# STB_Spectrometer.net
KiCad netlist of a schematic drawn in Altium Designer
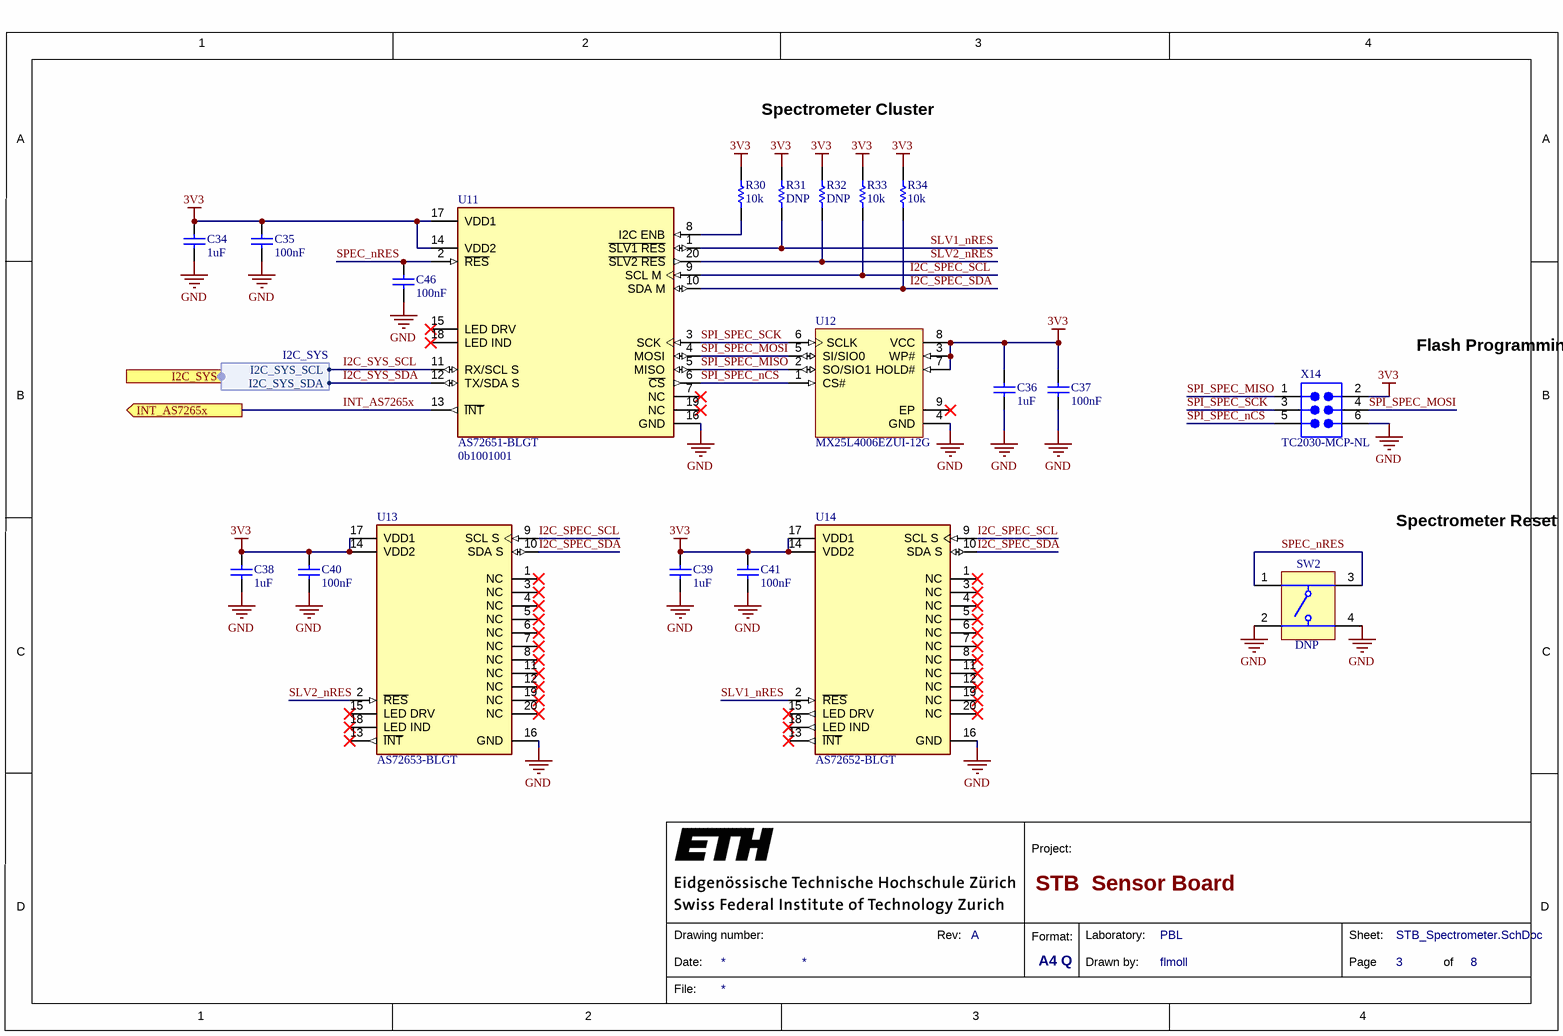
[diagram p0: STB_Spectrometer.SchDoc]

(export (version "E")
  (design (tool "Eeschema 10.0.6"))
  (components
    (comp (ref "C34")
      (value "1uF")
      (footprint "CAPC1608X90X35LL15T15")
      (fields (field (name "MANUFACTURER") "Kemet") (field (name "PART NUMBER") "C0603C105K4RACTU"))
      (libsource (lib "Altium Content Vault") (part "CAP"))
    )
    (comp (ref "C35")
      (value "100nF")
      (footprint "CAPC1050X55X23LL05T13")
      (description "Chip Capacitor, 100 nF, +/- 10%, 16 V, -55 to 125 degC, 0402 (1005 Metric), RoHS, Tape and Reel")
      (fields
        (field (name "MANUFACTURER") "Samsung Electro-Mechanics")
        (field (name "MANUFACTURER PART NUMBER") "CL05B104KO5NNNC")
      )
      (libsource (lib "Altium Content Vault") (part "CAP-NP-2"))
    )
    (comp (ref "C36")
      (value "1uF")
      (footprint "CAPC1608X90X35LL15T15")
      (fields (field (name "MANUFACTURER") "Kemet") (field (name "PART NUMBER") "C0603C105K4RACTU"))
      (libsource (lib "Altium Content Vault") (part "CAP"))
    )
    (comp (ref "C37")
      (value "100nF")
      (footprint "CAPC1050X55X23LL05T13")
      (description "Chip Capacitor, 100 nF, +/- 10%, 16 V, -55 to 125 degC, 0402 (1005 Metric), RoHS, Tape and Reel")
      (fields
        (field (name "MANUFACTURER") "Samsung Electro-Mechanics")
        (field (name "MANUFACTURER PART NUMBER") "CL05B104KO5NNNC")
      )
      (libsource (lib "Altium Content Vault") (part "CAP-NP-2"))
    )
    (comp (ref "C38")
      (value "1uF")
      (footprint "CAPC1608X90X35LL15T15")
      (fields (field (name "MANUFACTURER") "Kemet") (field (name "PART NUMBER") "C0603C105K4RACTU"))
      (libsource (lib "Altium Content Vault") (part "CAP"))
    )
    (comp (ref "C39")
      (value "1uF")
      (footprint "CAPC1608X90X35LL15T15")
      (fields (field (name "MANUFACTURER") "Kemet") (field (name "PART NUMBER") "C0603C105K4RACTU"))
      (libsource (lib "Altium Content Vault") (part "CAP"))
    )
    (comp (ref "C40")
      (value "100nF")
      (footprint "CAPC1050X55X23LL05T13")
      (description "Chip Capacitor, 100 nF, +/- 10%, 16 V, -55 to 125 degC, 0402 (1005 Metric), RoHS, Tape and Reel")
      (fields
        (field (name "MANUFACTURER") "Samsung Electro-Mechanics")
        (field (name "MANUFACTURER PART NUMBER") "CL05B104KO5NNNC")
      )
      (libsource (lib "Altium Content Vault") (part "CAP-NP-2"))
    )
    (comp (ref "C41")
      (value "100nF")
      (footprint "CAPC1050X55X23LL05T13")
      (description "Chip Capacitor, 100 nF, +/- 10%, 16 V, -55 to 125 degC, 0402 (1005 Metric), RoHS, Tape and Reel")
      (fields
        (field (name "MANUFACTURER") "Samsung Electro-Mechanics")
        (field (name "MANUFACTURER PART NUMBER") "CL05B104KO5NNNC")
      )
      (libsource (lib "Altium Content Vault") (part "CAP-NP-2"))
    )
    (comp (ref "C46")
      (value "100nF")
      (footprint "CAPC1050X55X23LL05T13")
      (description "Chip Capacitor, 100 nF, +/- 10%, 16 V, -55 to 125 degC, 0402 (1005 Metric), RoHS, Tape and Reel")
      (fields
        (field (name "MANUFACTURER") "Samsung Electro-Mechanics")
        (field (name "MANUFACTURER PART NUMBER") "CL05B104KO5NNNC")
      )
      (libsource (lib "Altium Content Vault") (part "CAP-NP-2"))
    )
    (comp (ref "R30")
      (value "10k")
      (footprint "RESC1005X40X25LL05T05")
      (description "Chip Resistor, 10 KOhm, +/- 1%, 0.1 W, -55 to 155 degC, 0402 (1005 Metric), RoHS, Tape and Reel")
      (fields (field (name "TOLERANCE") "1%") (field (name "MANUFACTURER") "Panasonic"))
      (libsource (lib "Altium Content Vault") (part "RES-2"))
    )
    (comp (ref "R31")
      (value "DNP")
      (footprint "RESC1005X40X25LL05T05")
      (description "Chip Resistor, 10 KOhm, +/- 1%, 0.1 W, -55 to 155 degC, 0402 (1005 Metric), RoHS, Tape and Reel")
      (fields (field (name "TOLERANCE") "1%") (field (name "MANUFACTURER") "Panasonic"))
      (libsource (lib "Altium Content Vault") (part "RES-2"))
    )
    (comp (ref "R32")
      (value "DNP")
      (footprint "RESC1005X40X25LL05T05")
      (description "Chip Resistor, 10 KOhm, +/- 1%, 0.1 W, -55 to 155 degC, 0402 (1005 Metric), RoHS, Tape and Reel")
      (fields (field (name "TOLERANCE") "1%") (field (name "MANUFACTURER") "Panasonic"))
      (libsource (lib "Altium Content Vault") (part "RES-2"))
    )
    (comp (ref "R33")
      (value "10k")
      (footprint "RESC1005X40X25LL05T05")
      (description "Chip Resistor, 10 KOhm, +/- 1%, 0.1 W, -55 to 155 degC, 0402 (1005 Metric), RoHS, Tape and Reel")
      (fields (field (name "TOLERANCE") "1%") (field (name "MANUFACTURER") "Panasonic"))
      (libsource (lib "Altium Content Vault") (part "RES-2"))
    )
    (comp (ref "R34")
      (value "10k")
      (footprint "RESC1005X40X25LL05T05")
      (description "Chip Resistor, 10 KOhm, +/- 1%, 0.1 W, -55 to 155 degC, 0402 (1005 Metric), RoHS, Tape and Reel")
      (fields (field (name "TOLERANCE") "1%") (field (name "MANUFACTURER") "Panasonic"))
      (libsource (lib "Altium Content Vault") (part "RES-2"))
    )
    (comp (ref "SW2")
      (value "DNP")
      (footprint "PNSC-EVPAA_V")
      (description "Light Touch Switch, 100 mOhm, -40 to 85 degC, 4-Pin SMD, RoHS, Tape and Reel")
      (fields (field (name "MANUFACTURER") "Panasonic") (field (name "PART NO") "EVP-AA002K"))
      (libsource (lib "Altium Content Vault") (part "SW-SPST-4"))
    )
    (comp (ref "U11")
      (value "AS72651-BLGT")
      (footprint "FP-AS72651-BLGT-MFG")
      (description "AS72651-BLGT LGA20 LF T&RDP")
      (fields (field (name "MANUFACTURER") "ams") (field (name "ADDRESS") "0b1001001"))
      (libsource (lib "Altium Content Vault") (part "96c49a94035c55414f36293780c885a"))
    )
    (comp (ref "U12")
      (value "MX25L4006EZUI-12G")
      (footprint "MXIC-USON-8_V")
      (description "4 M-Bit [x1 / x2] CMOS Serial Flash, 86 MHz, -0.7 to 3.6 V, -40 to 85 degC, Body  2 x 3 x 0.6 mm")
      (fields (field (name "MANUFACTURER") "Macronix"))
      (libsource (lib "Altium Content Vault") (part "MXIC-MX25L4006EZUI-12G-USON-8"))
    )
    (comp (ref "U13")
      (value "AS72653-BLGT")
      (footprint "FP-AS72653-BLGT-MFG")
      (description "AS72653-BLGT LGA20 LF T&RDP")
      (fields (field (name "MANUFACTURER") "ams"))
      (libsource (lib "Altium Content Vault") (part "dbaf3b1d840af62113c8d089df4a8dc"))
    )
    (comp (ref "U14")
      (value "AS72652-BLGT")
      (footprint "FP-AS72652-BLGT-MFG")
      (description "AS72652-BLGT LGA20 LF T&RDP")
      (fields (field (name "MANUFACTURER") "ams"))
      (libsource (lib "Altium Content Vault") (part "071b443b34d8799e7ba01a9bef9e0b3"))
    )
    (comp (ref "X14")
      (value "TC2030-MCP-NL")
      (footprint "TC2030-MCP-NL")
      (description "CABLE, TAG CONNECT, WITH OUT LEG, FOR IC")
      (libsource (lib "ETHZ Vault") (part "CON-3x2-Male"))
    )
  )
  (nets
    (net (code "2") (name "/I2C_SPEC_SCL") (class "Default")
      (node (ref "R33") (pin "1") (pinfunction "1_1") (pintype "passive"))
      (node (ref "U11") (pin "9") (pinfunction "SCL_M_9") (pintype "input"))
      (node (ref "U13") (pin "9") (pinfunction "SCL_S_9") (pintype "input"))
      (node (ref "U14") (pin "9") (pinfunction "SCL_S_9") (pintype "input"))
    )
    (net (code "3") (name "/I2C_SPEC_SDA") (class "Default")
      (node (ref "R34") (pin "1") (pinfunction "1_1") (pintype "passive"))
      (node (ref "U11") (pin "10") (pinfunction "SDA_M_10") (pintype "bidirectional"))
      (node (ref "U13") (pin "10") (pinfunction "SDA_S_10") (pintype "bidirectional"))
      (node (ref "U14") (pin "10") (pinfunction "SDA_S_10") (pintype "bidirectional"))
    )
    (net (code "4") (name "/I2C_SYS_SCL") (class "Default")
      (node (ref "U11") (pin "11") (pinfunction "RX/SCL_S_11") (pintype "bidirectional"))
    )
    (net (code "5") (name "/I2C_SYS_SDA") (class "Default")
      (node (ref "U11") (pin "12") (pinfunction "TX/SDA_S_12") (pintype "bidirectional"))
    )
    (net (code "6") (name "/INT_AS7265x") (class "Default")
      (node (ref "U11") (pin "13") (pinfunction "~{INT}_13") (pintype "output"))
    )
    (net (code "7") (name "/SLV1_nRES") (class "Default")
      (node (ref "R31") (pin "1") (pinfunction "1_1") (pintype "passive"))
      (node (ref "U11") (pin "1") (pinfunction "~{SLV1_RES}_1") (pintype "bidirectional"))
      (node (ref "U14") (pin "2") (pinfunction "~{RES}_2") (pintype "input"))
    )
    (net (code "8") (name "/SLV2_nRES") (class "Default")
      (node (ref "R32") (pin "1") (pinfunction "1_1") (pintype "passive"))
      (node (ref "U11") (pin "20") (pinfunction "~{SLV2_RES}_20") (pintype "output"))
      (node (ref "U13") (pin "2") (pinfunction "~{RES}_2") (pintype "input"))
    )
    (net (code "9") (name "/SPEC_nRES") (class "Default")
      (node (ref "C46") (pin "2") (pinfunction "2_2") (pintype "passive"))
      (node (ref "SW2") (pin "1") (pinfunction "A_1") (pintype "passive"))
      (node (ref "SW2") (pin "3") (pinfunction "A'_3") (pintype "passive"))
      (node (ref "U11") (pin "2") (pinfunction "~{RES}_2") (pintype "input"))
    )
    (net (code "10") (name "/SPI_SPEC_MISO") (class "Default")
      (node (ref "U11") (pin "5") (pinfunction "MISO_5") (pintype "bidirectional"))
      (node (ref "U12") (pin "2") (pinfunction "SO/SIO1_2") (pintype "bidirectional"))
      (node (ref "X14") (pin "1") (pinfunction "1_1") (pintype "passive"))
    )
    (net (code "11") (name "/SPI_SPEC_MOSI") (class "Default")
      (node (ref "U11") (pin "4") (pinfunction "MOSI_4") (pintype "bidirectional"))
      (node (ref "U12") (pin "5") (pinfunction "SI/SIO0_5") (pintype "bidirectional"))
      (node (ref "X14") (pin "4") (pinfunction "4_4") (pintype "passive"))
    )
    (net (code "12") (name "/SPI_SPEC_SCK") (class "Default")
      (node (ref "U11") (pin "3") (pinfunction "SCK_3") (pintype "input"))
      (node (ref "U12") (pin "6") (pinfunction "SCLK_6") (pintype "input"))
      (node (ref "X14") (pin "3") (pinfunction "3_3") (pintype "passive"))
    )
    (net (code "13") (name "/SPI_SPEC_nCS") (class "Default")
      (node (ref "U11") (pin "6") (pinfunction "~{CS}_6") (pintype "output"))
      (node (ref "U12") (pin "1") (pinfunction "CS#_1") (pintype "input"))
      (node (ref "X14") (pin "5") (pinfunction "5_5") (pintype "passive"))
    )
    (net (code "15") (name "3V3") (class "Default")
      (node (ref "C34") (pin "2") (pinfunction "2_2") (pintype "passive"))
      (node (ref "C35") (pin "2") (pinfunction "2_2") (pintype "passive"))
      (node (ref "C36") (pin "2") (pinfunction "2_2") (pintype "passive"))
      (node (ref "C37") (pin "2") (pinfunction "2_2") (pintype "passive"))
      (node (ref "C38") (pin "2") (pinfunction "2_2") (pintype "passive"))
      (node (ref "C39") (pin "2") (pinfunction "2_2") (pintype "passive"))
      (node (ref "C40") (pin "2") (pinfunction "2_2") (pintype "passive"))
      (node (ref "C41") (pin "2") (pinfunction "2_2") (pintype "passive"))
      (node (ref "R30") (pin "2") (pinfunction "2_2") (pintype "passive"))
      (node (ref "R31") (pin "2") (pinfunction "2_2") (pintype "passive"))
      (node (ref "R32") (pin "2") (pinfunction "2_2") (pintype "passive"))
      (node (ref "R33") (pin "2") (pinfunction "2_2") (pintype "passive"))
      (node (ref "R34") (pin "2") (pinfunction "2_2") (pintype "passive"))
      (node (ref "U11") (pin "14") (pinfunction "VDD2_14") (pintype "power_in"))
      (node (ref "U11") (pin "17") (pinfunction "VDD1_17") (pintype "power_in"))
      (node (ref "U12") (pin "3") (pinfunction "WP#_3") (pintype "input"))
      (node (ref "U12") (pin "7") (pinfunction "HOLD#_7") (pintype "input"))
      (node (ref "U12") (pin "8") (pinfunction "VCC_8") (pintype "power_in"))
      (node (ref "U13") (pin "14") (pinfunction "VDD2_14") (pintype "power_in"))
      (node (ref "U13") (pin "17") (pinfunction "VDD1_17") (pintype "power_in"))
      (node (ref "U14") (pin "14") (pinfunction "VDD2_14") (pintype "power_in"))
      (node (ref "U14") (pin "17") (pinfunction "VDD1_17") (pintype "power_in"))
      (node (ref "X14") (pin "2") (pinfunction "2_2") (pintype "passive"))
    )
    (net (code "16") (name "GND") (class "Default")
      (node (ref "C34") (pin "1") (pinfunction "1_1") (pintype "passive"))
      (node (ref "C35") (pin "1") (pinfunction "1_1") (pintype "passive"))
      (node (ref "C36") (pin "1") (pinfunction "1_1") (pintype "passive"))
      (node (ref "C37") (pin "1") (pinfunction "1_1") (pintype "passive"))
      (node (ref "C38") (pin "1") (pinfunction "1_1") (pintype "passive"))
      (node (ref "C39") (pin "1") (pinfunction "1_1") (pintype "passive"))
      (node (ref "C40") (pin "1") (pinfunction "1_1") (pintype "passive"))
      (node (ref "C41") (pin "1") (pinfunction "1_1") (pintype "passive"))
      (node (ref "C46") (pin "1") (pinfunction "1_1") (pintype "passive"))
      (node (ref "SW2") (pin "2") (pinfunction "B_2") (pintype "passive"))
      (node (ref "SW2") (pin "4") (pinfunction "B'_4") (pintype "passive"))
      (node (ref "U11") (pin "16") (pinfunction "GND_16") (pintype "power_in"))
      (node (ref "U12") (pin "4") (pinfunction "GND_4") (pintype "power_in"))
      (node (ref "U13") (pin "16") (pinfunction "GND_16") (pintype "power_in"))
      (node (ref "U14") (pin "16") (pinfunction "GND_16") (pintype "power_in"))
      (node (ref "X14") (pin "6") (pinfunction "6_6") (pintype "passive"))
    )
    (net (code "17") (name "Net-(U11-I2C_ENB)") (class "Default")
      (node (ref "R30") (pin "1") (pinfunction "1_1") (pintype "passive"))
      (node (ref "U11") (pin "8") (pinfunction "I2C_ENB_8") (pintype "input"))
    )
    (net (code "18") (name "unconnected-(U11-LED_DRV-Pad15)") (class "Default")
      (node (ref "U11") (pin "15") (pinfunction "LED_DRV_15") (pintype "passive+no_connect"))
    )
    (net (code "19") (name "unconnected-(U11-LED_IND-Pad18)") (class "Default")
      (node (ref "U11") (pin "18") (pinfunction "LED_IND_18") (pintype "passive+no_connect"))
    )
    (net (code "20") (name "unconnected-(U11-NC-Pad7)") (class "Default")
      (node (ref "U11") (pin "7") (pinfunction "NC_7") (pintype "passive+no_connect"))
    )
    (net (code "21") (name "unconnected-(U11-NC-Pad19)") (class "Default")
      (node (ref "U11") (pin "19") (pinfunction "NC_19") (pintype "passive+no_connect"))
    )
    (net (code "22") (name "unconnected-(U12-EP-Pad9)") (class "Default")
      (node (ref "U12") (pin "9") (pinfunction "EP_9") (pintype "passive+no_connect"))
    )
    (net (code "23") (name "unconnected-(U13-LED_DRV-Pad15)") (class "Default")
      (node (ref "U13") (pin "15") (pinfunction "LED_DRV_15") (pintype "passive+no_connect"))
    )
    (net (code "24") (name "unconnected-(U13-LED_IND-Pad18)") (class "Default")
      (node (ref "U13") (pin "18") (pinfunction "LED_IND_18") (pintype "passive+no_connect"))
    )
    (net (code "25") (name "unconnected-(U13-NC-Pad1)") (class "Default")
      (node (ref "U13") (pin "1") (pinfunction "NC_1") (pintype "passive+no_connect"))
    )
    (net (code "26") (name "unconnected-(U13-NC-Pad3)") (class "Default")
      (node (ref "U13") (pin "3") (pinfunction "NC_3") (pintype "passive+no_connect"))
    )
    (net (code "27") (name "unconnected-(U13-NC-Pad4)") (class "Default")
      (node (ref "U13") (pin "4") (pinfunction "NC_4") (pintype "passive+no_connect"))
    )
    (net (code "28") (name "unconnected-(U13-NC-Pad5)") (class "Default")
      (node (ref "U13") (pin "5") (pinfunction "NC_5") (pintype "passive+no_connect"))
    )
    (net (code "29") (name "unconnected-(U13-NC-Pad6)") (class "Default")
      (node (ref "U13") (pin "6") (pinfunction "NC_6") (pintype "passive+no_connect"))
    )
    (net (code "30") (name "unconnected-(U13-NC-Pad7)") (class "Default")
      (node (ref "U13") (pin "7") (pinfunction "NC_7") (pintype "passive+no_connect"))
    )
    (net (code "31") (name "unconnected-(U13-NC-Pad8)") (class "Default")
      (node (ref "U13") (pin "8") (pinfunction "NC_8") (pintype "passive+no_connect"))
    )
    (net (code "32") (name "unconnected-(U13-NC-Pad11)") (class "Default")
      (node (ref "U13") (pin "11") (pinfunction "NC_11") (pintype "passive+no_connect"))
    )
    (net (code "33") (name "unconnected-(U13-NC-Pad12)") (class "Default")
      (node (ref "U13") (pin "12") (pinfunction "NC_12") (pintype "passive+no_connect"))
    )
    (net (code "34") (name "unconnected-(U13-NC-Pad19)") (class "Default")
      (node (ref "U13") (pin "19") (pinfunction "NC_19") (pintype "passive+no_connect"))
    )
    (net (code "35") (name "unconnected-(U13-NC-Pad20)") (class "Default")
      (node (ref "U13") (pin "20") (pinfunction "NC_20") (pintype "passive+no_connect"))
    )
    (net (code "36") (name "unconnected-(U13-~{INT}-Pad13)") (class "Default")
      (node (ref "U13") (pin "13") (pinfunction "~{INT}_13") (pintype "output+no_connect"))
    )
    (net (code "37") (name "unconnected-(U14-LED_DRV-Pad15)") (class "Default")
      (node (ref "U14") (pin "15") (pinfunction "LED_DRV_15") (pintype "output+no_connect"))
    )
    (net (code "38") (name "unconnected-(U14-LED_IND-Pad18)") (class "Default")
      (node (ref "U14") (pin "18") (pinfunction "LED_IND_18") (pintype "output+no_connect"))
    )
    (net (code "39") (name "unconnected-(U14-NC-Pad1)") (class "Default")
      (node (ref "U14") (pin "1") (pinfunction "NC_1") (pintype "passive+no_connect"))
    )
    (net (code "40") (name "unconnected-(U14-NC-Pad3)") (class "Default")
      (node (ref "U14") (pin "3") (pinfunction "NC_3") (pintype "passive+no_connect"))
    )
    (net (code "41") (name "unconnected-(U14-NC-Pad4)") (class "Default")
      (node (ref "U14") (pin "4") (pinfunction "NC_4") (pintype "passive+no_connect"))
    )
    (net (code "42") (name "unconnected-(U14-NC-Pad5)") (class "Default")
      (node (ref "U14") (pin "5") (pinfunction "NC_5") (pintype "passive+no_connect"))
    )
    (net (code "43") (name "unconnected-(U14-NC-Pad6)") (class "Default")
      (node (ref "U14") (pin "6") (pinfunction "NC_6") (pintype "passive+no_connect"))
    )
    (net (code "44") (name "unconnected-(U14-NC-Pad7)") (class "Default")
      (node (ref "U14") (pin "7") (pinfunction "NC_7") (pintype "passive+no_connect"))
    )
    (net (code "45") (name "unconnected-(U14-NC-Pad8)") (class "Default")
      (node (ref "U14") (pin "8") (pinfunction "NC_8") (pintype "passive+no_connect"))
    )
    (net (code "46") (name "unconnected-(U14-NC-Pad11)") (class "Default")
      (node (ref "U14") (pin "11") (pinfunction "NC_11") (pintype "passive+no_connect"))
    )
    (net (code "47") (name "unconnected-(U14-NC-Pad12)") (class "Default")
      (node (ref "U14") (pin "12") (pinfunction "NC_12") (pintype "passive+no_connect"))
    )
    (net (code "48") (name "unconnected-(U14-NC-Pad19)") (class "Default")
      (node (ref "U14") (pin "19") (pinfunction "NC_19") (pintype "passive+no_connect"))
    )
    (net (code "49") (name "unconnected-(U14-NC-Pad20)") (class "Default")
      (node (ref "U14") (pin "20") (pinfunction "NC_20") (pintype "passive+no_connect"))
    )
    (net (code "50") (name "unconnected-(U14-~{INT}-Pad13)") (class "Default")
      (node (ref "U14") (pin "13") (pinfunction "~{INT}_13") (pintype "output+no_connect"))
    )
  )
)
